# itrope-serial-v05.net
KiCad netlist of a schematic drawn in EAGLE
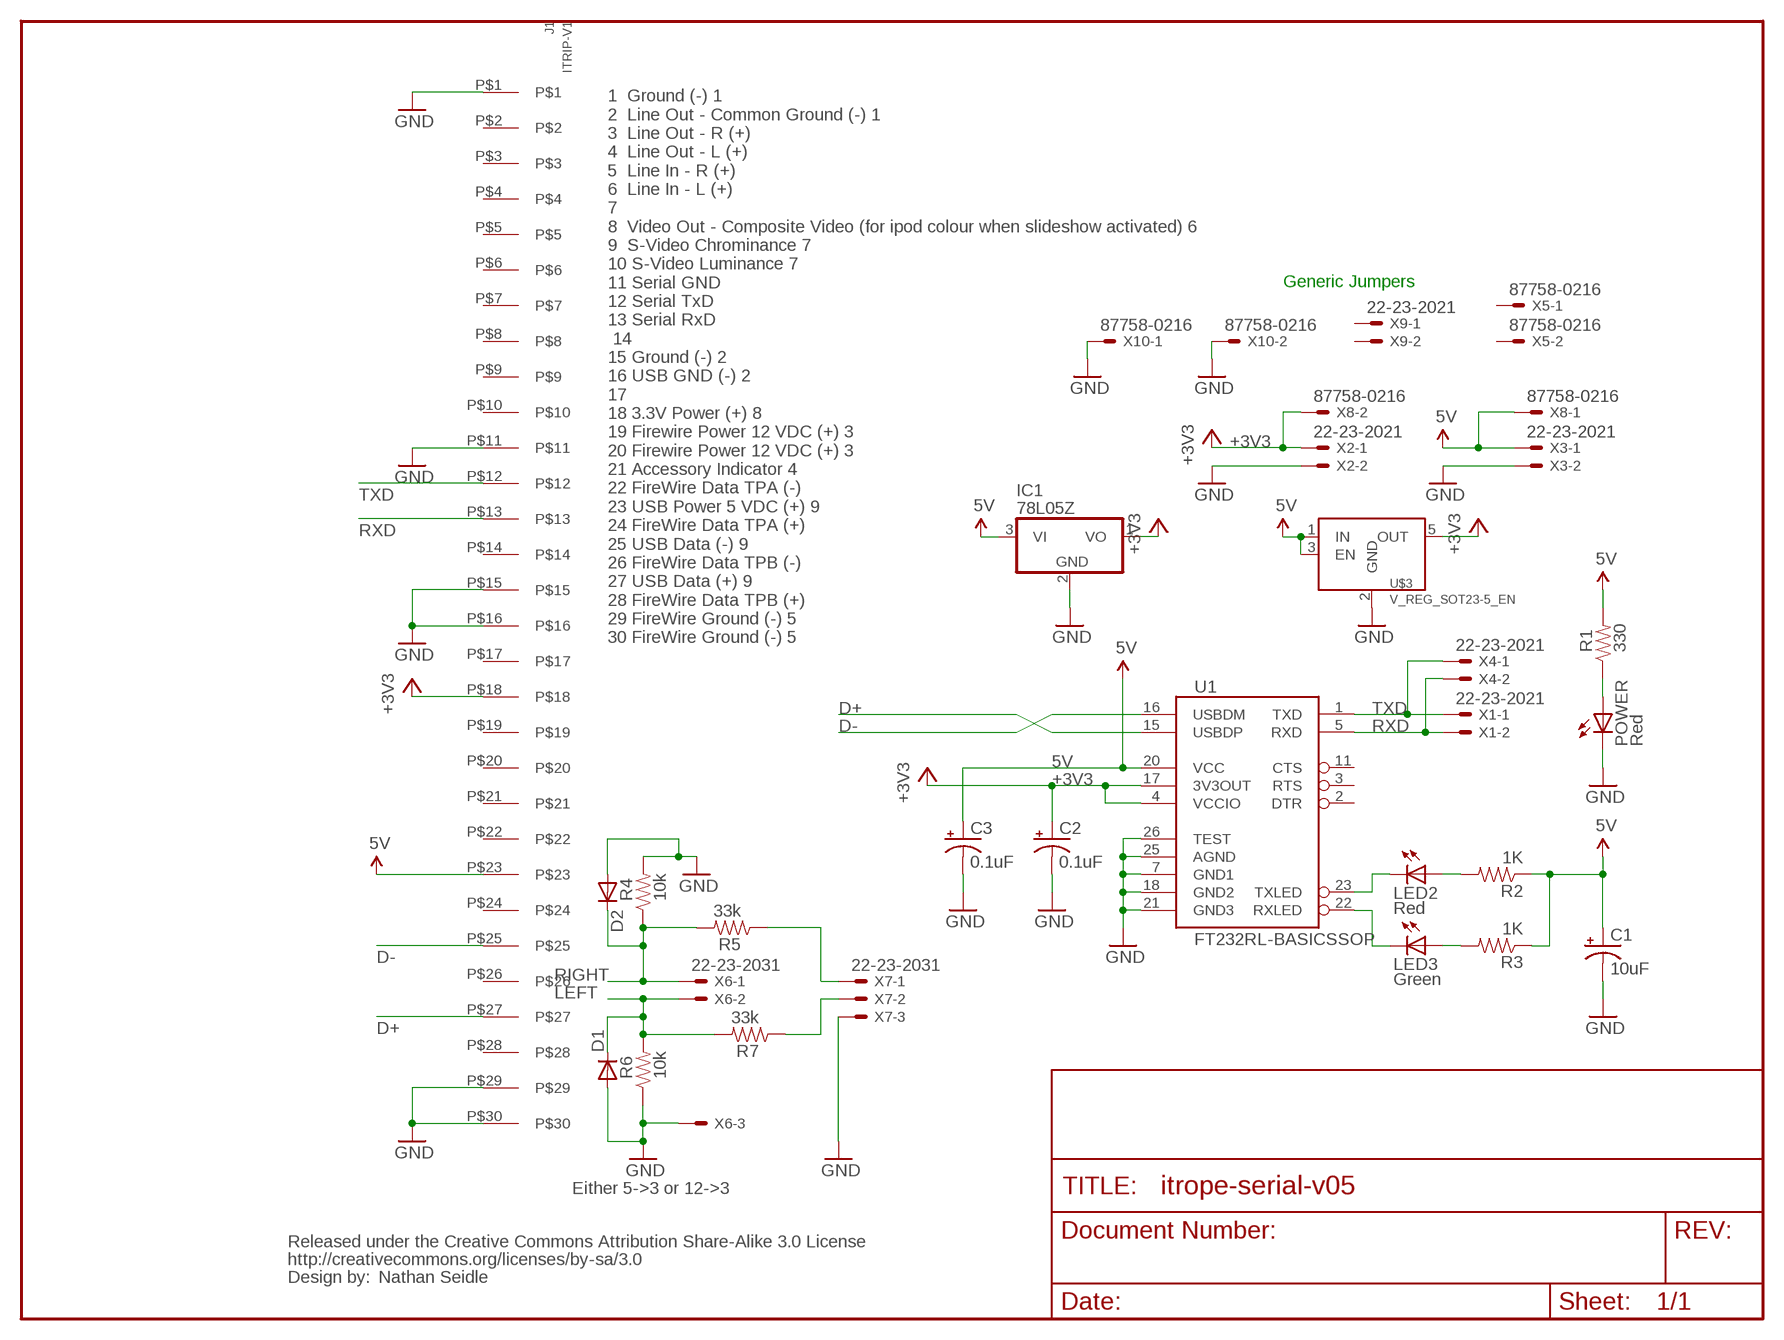
[diagram p0: schematic, sheet 1]

(export (version "E")
  (design (tool "Eeschema 10.0.6"))
  (components
    (comp (ref "C1")
      (value "10uF")
      (footprint "eagle-import:E2,5-5")
      (libsource (lib "eagle-import") (part "CPOL-USE2.5-5"))
    )
    (comp (ref "C2")
      (value "0.1uF")
      (footprint "eagle-import:E2,5-5")
      (libsource (lib "eagle-import") (part "CPOL-USE2.5-5"))
    )
    (comp (ref "C3")
      (value "0.1uF")
      (footprint "eagle-import:E2,5-5")
      (libsource (lib "eagle-import") (part "CPOL-USE2.5-5"))
    )
    (comp (ref "D1")
      (value "DIODESOD")
      (footprint "eagle-import:SOD-323")
      (libsource (lib "eagle-import") (part "DIODESOD"))
    )
    (comp (ref "D2")
      (value "DIODESOD")
      (footprint "eagle-import:SOD-323")
      (libsource (lib "eagle-import") (part "DIODESOD"))
    )
    (comp (ref "IC1")
      (value "78L05Z")
      (footprint "eagle-import:TO92")
      (libsource (lib "eagle-import") (part "78ZL05"))
    )
    (comp (ref "J1")
      (value "ITRIP-V1")
      (footprint "eagle-import:30PINEDGE+ITRIP")
      (libsource (lib "eagle-import") (part "ITRIP-V1"))
    )
    (comp (ref "LED2")
      (value "Red")
      (footprint "eagle-import:LED-0603")
      (libsource (lib "eagle-import") (part "LED0603"))
    )
    (comp (ref "LED3")
      (value "Green")
      (footprint "eagle-import:LED-0603")
      (libsource (lib "eagle-import") (part "LED0603"))
    )
    (comp (ref "POWER")
      (value "Red")
      (footprint "eagle-import:LED-0603")
      (libsource (lib "eagle-import") (part "LED0603"))
    )
    (comp (ref "R1")
      (value "330")
      (footprint "eagle-import:C0402")
      (libsource (lib "eagle-import") (part "RESISTOR0402"))
    )
    (comp (ref "R2")
      (value "1K")
      (footprint "eagle-import:C0402")
      (libsource (lib "eagle-import") (part "RESISTOR0402"))
    )
    (comp (ref "R3")
      (value "1K")
      (footprint "eagle-import:C0402")
      (libsource (lib "eagle-import") (part "RESISTOR0402"))
    )
    (comp (ref "R4")
      (value "10k")
      (footprint "eagle-import:C0402")
      (libsource (lib "eagle-import") (part "RESISTOR0402"))
    )
    (comp (ref "R5")
      (value "33k")
      (footprint "eagle-import:C0402")
      (libsource (lib "eagle-import") (part "RESISTOR0402"))
    )
    (comp (ref "R6")
      (value "10k")
      (footprint "eagle-import:C0402")
      (libsource (lib "eagle-import") (part "RESISTOR0402"))
    )
    (comp (ref "R7")
      (value "33k")
      (footprint "eagle-import:C0402")
      (libsource (lib "eagle-import") (part "RESISTOR0402"))
    )
    (comp (ref "U$3")
      (value "V_REG_SOT23-5_EN")
      (footprint "eagle-import:SOT23-5")
      (libsource (lib "eagle-import") (part "V_REG_SOT23-5_EN"))
    )
    (comp (ref "U$9")
      (value "CREATIVE_COMMONS")
      (footprint "eagle-import:CREATIVE_COMMONS")
      (libsource (lib "eagle-import") (part "CREATIVE_COMMONS"))
    )
    (comp (ref "U1")
      (value "FT232RL-BASICSSOP")
      (footprint "eagle-import:SSOP28DB")
      (libsource (lib "eagle-import") (part "FT232RL-BASICSSOP"))
    )
    (comp (ref "X1")
      (value "22-23-2021")
      (footprint "eagle-import:22-23-2021")
      (fields (field (name "MF") "MOLEX"))
      (libsource (lib "eagle-import") (part "22-23-2021"))
    )
    (comp (ref "X2")
      (value "22-23-2021")
      (footprint "eagle-import:22-23-2021")
      (fields (field (name "MF") "MOLEX"))
      (libsource (lib "eagle-import") (part "22-23-2021"))
    )
    (comp (ref "X3")
      (value "22-23-2021")
      (footprint "eagle-import:22-23-2021")
      (fields (field (name "MF") "MOLEX"))
      (libsource (lib "eagle-import") (part "22-23-2021"))
    )
    (comp (ref "X4")
      (value "22-23-2021")
      (footprint "eagle-import:22-23-2021")
      (fields (field (name "MF") "MOLEX"))
      (libsource (lib "eagle-import") (part "22-23-2021"))
    )
    (comp (ref "X5")
      (value "87758-0216")
      (footprint "eagle-import:87758-0216")
      (libsource (lib "eagle-import") (part "87758-0216"))
    )
    (comp (ref "X6")
      (value "22-23-2031")
      (footprint "eagle-import:22-23-2031")
      (fields (field (name "MF") "MOLEX"))
      (libsource (lib "eagle-import") (part "22-23-2031"))
    )
    (comp (ref "X7")
      (value "22-23-2031")
      (footprint "eagle-import:22-23-2031")
      (fields (field (name "MF") "MOLEX"))
      (libsource (lib "eagle-import") (part "22-23-2031"))
    )
    (comp (ref "X8")
      (value "87758-0216")
      (footprint "eagle-import:87758-0216")
      (libsource (lib "eagle-import") (part "87758-0216"))
    )
    (comp (ref "X9")
      (value "22-23-2021")
      (footprint "eagle-import:22-23-2021")
      (fields (field (name "MF") "MOLEX"))
      (libsource (lib "eagle-import") (part "22-23-2021"))
    )
    (comp (ref "X10")
      (value "87758-0216")
      (footprint "eagle-import:87758-0216")
      (libsource (lib "eagle-import") (part "87758-0216"))
    )
  )
  (nets
    (net (code "1") (name "+3V3") (class "Default")
      (node (ref "C2") (pin "+") (pinfunction "+_+") (pintype "passive"))
      (node (ref "IC1") (pin "1") (pinfunction "VO_1") (pintype "passive"))
      (node (ref "J1") (pin "P$18") (pinfunction "P$18_P$18") (pintype "bidirectional"))
      (node (ref "U$3") (pin "5") (pinfunction "OUT_5") (pintype "passive"))
      (node (ref "U1") (pin "17") (pinfunction "3V3OUT_17") (pintype "output"))
      (node (ref "U1") (pin "4") (pinfunction "VCCIO_4") (pintype "power_in"))
      (node (ref "X2") (pin "1") (pinfunction "S_1") (pintype "passive"))
      (node (ref "X8") (pin "2") (pinfunction "S_2") (pintype "passive"))
    )
    (net (code "2") (name "/D+") (class "Default")
      (node (ref "J1") (pin "P$27") (pinfunction "P$27_P$27") (pintype "bidirectional"))
      (node (ref "U1") (pin "15") (pinfunction "USBDP_15") (pintype "bidirectional"))
    )
    (net (code "3") (name "/D-") (class "Default")
      (node (ref "J1") (pin "P$25") (pinfunction "P$25_P$25") (pintype "bidirectional"))
      (node (ref "U1") (pin "16") (pinfunction "USBDM_16") (pintype "bidirectional"))
    )
    (net (code "4") (name "/LEFT") (class "Default")
      (node (ref "D1") (pin "1") (pinfunction "C_1") (pintype "passive"))
      (node (ref "R6") (pin "2") (pinfunction "2_2") (pintype "passive"))
      (node (ref "R7") (pin "2") (pinfunction "2_2") (pintype "passive"))
      (node (ref "X6") (pin "2") (pinfunction "S_2") (pintype "passive"))
    )
    (net (code "5") (name "/RIGHT") (class "Default")
      (node (ref "D2") (pin "1") (pinfunction "C_1") (pintype "passive"))
      (node (ref "R4") (pin "1") (pinfunction "1_1") (pintype "passive"))
      (node (ref "R5") (pin "2") (pinfunction "2_2") (pintype "passive"))
      (node (ref "X6") (pin "1") (pinfunction "S_1") (pintype "passive"))
    )
    (net (code "6") (name "/RXD") (class "Default")
      (node (ref "J1") (pin "P$13") (pinfunction "P$13_P$13") (pintype "bidirectional"))
      (node (ref "U1") (pin "5") (pinfunction "RXD_5") (pintype "input"))
      (node (ref "X1") (pin "2") (pinfunction "S_2") (pintype "passive"))
      (node (ref "X4") (pin "2") (pinfunction "S_2") (pintype "passive"))
    )
    (net (code "7") (name "/TXD") (class "Default")
      (node (ref "J1") (pin "P$12") (pinfunction "P$12_P$12") (pintype "bidirectional"))
      (node (ref "U1") (pin "1") (pinfunction "TXD_1") (pintype "output"))
      (node (ref "X1") (pin "1") (pinfunction "S_1") (pintype "passive"))
      (node (ref "X4") (pin "1") (pinfunction "S_1") (pintype "passive"))
    )
    (net (code "8") (name "5V") (class "Default")
      (node (ref "C1") (pin "+") (pinfunction "+_+") (pintype "passive"))
      (node (ref "C3") (pin "+") (pinfunction "+_+") (pintype "passive"))
      (node (ref "IC1") (pin "3") (pinfunction "VI_3") (pintype "input"))
      (node (ref "J1") (pin "P$23") (pinfunction "P$23_P$23") (pintype "bidirectional"))
      (node (ref "R1") (pin "2") (pinfunction "2_2") (pintype "passive"))
      (node (ref "R2") (pin "1") (pinfunction "1_1") (pintype "passive"))
      (node (ref "R3") (pin "1") (pinfunction "1_1") (pintype "passive"))
      (node (ref "U$3") (pin "1") (pinfunction "IN_1") (pintype "input"))
      (node (ref "U$3") (pin "3") (pinfunction "EN_3") (pintype "input"))
      (node (ref "U1") (pin "20") (pinfunction "VCC_20") (pintype "power_in"))
      (node (ref "X3") (pin "1") (pinfunction "S_1") (pintype "passive"))
      (node (ref "X8") (pin "1") (pinfunction "S_1") (pintype "passive"))
    )
    (net (code "9") (name "GND") (class "Default")
      (node (ref "C1") (pin "-") (pinfunction "-_-") (pintype "passive"))
      (node (ref "C2") (pin "-") (pinfunction "-_-") (pintype "passive"))
      (node (ref "C3") (pin "-") (pinfunction "-_-") (pintype "passive"))
      (node (ref "D1") (pin "2") (pinfunction "A_2") (pintype "passive"))
      (node (ref "D2") (pin "2") (pinfunction "A_2") (pintype "passive"))
      (node (ref "IC1") (pin "2") (pinfunction "GND_2") (pintype "passive"))
      (node (ref "J1") (pin "P$1") (pinfunction "P$1_P$1") (pintype "bidirectional"))
      (node (ref "J1") (pin "P$11") (pinfunction "P$11_P$11") (pintype "bidirectional"))
      (node (ref "J1") (pin "P$15") (pinfunction "P$15_P$15") (pintype "bidirectional"))
      (node (ref "J1") (pin "P$16") (pinfunction "P$16_P$16") (pintype "bidirectional"))
      (node (ref "J1") (pin "P$29") (pinfunction "P$29_P$29") (pintype "bidirectional"))
      (node (ref "J1") (pin "P$30") (pinfunction "P$30_P$30") (pintype "bidirectional"))
      (node (ref "POWER") (pin "C") (pinfunction "C_C") (pintype "passive"))
      (node (ref "R4") (pin "2") (pinfunction "2_2") (pintype "passive"))
      (node (ref "R6") (pin "1") (pinfunction "1_1") (pintype "passive"))
      (node (ref "U$3") (pin "2") (pinfunction "GND_2") (pintype "input"))
      (node (ref "U1") (pin "18") (pinfunction "GND2_18") (pintype "power_in"))
      (node (ref "U1") (pin "21") (pinfunction "GND3_21") (pintype "power_in"))
      (node (ref "U1") (pin "25") (pinfunction "AGND_25") (pintype "power_in"))
      (node (ref "U1") (pin "26") (pinfunction "TEST_26") (pintype "input"))
      (node (ref "U1") (pin "7") (pinfunction "GND1_7") (pintype "power_in"))
      (node (ref "X10") (pin "1") (pinfunction "S_1") (pintype "passive"))
      (node (ref "X10") (pin "2") (pinfunction "S_2") (pintype "passive"))
      (node (ref "X2") (pin "2") (pinfunction "S_2") (pintype "passive"))
      (node (ref "X3") (pin "2") (pinfunction "S_2") (pintype "passive"))
      (node (ref "X6") (pin "3") (pinfunction "S_3") (pintype "passive"))
      (node (ref "X7") (pin "3") (pinfunction "S_3") (pintype "passive"))
    )
    (net (code "10") (name "Net-(LED2-PadA)") (class "Default")
      (node (ref "LED2") (pin "A") (pinfunction "A_A") (pintype "passive"))
      (node (ref "R2") (pin "2") (pinfunction "2_2") (pintype "passive"))
    )
    (net (code "11") (name "Net-(LED3-PadA)") (class "Default")
      (node (ref "LED3") (pin "A") (pinfunction "A_A") (pintype "passive"))
      (node (ref "R3") (pin "2") (pinfunction "2_2") (pintype "passive"))
    )
    (net (code "12") (name "Net-(POWER-PadA)") (class "Default")
      (node (ref "POWER") (pin "A") (pinfunction "A_A") (pintype "passive"))
      (node (ref "R1") (pin "1") (pinfunction "1_1") (pintype "passive"))
    )
    (net (code "13") (name "Net-(U1-RXLED)") (class "Default")
      (node (ref "LED3") (pin "C") (pinfunction "C_C") (pintype "passive"))
      (node (ref "U1") (pin "22") (pinfunction "RXLED_22") (pintype "bidirectional"))
    )
    (net (code "14") (name "Net-(U1-TXLED)") (class "Default")
      (node (ref "LED2") (pin "C") (pinfunction "C_C") (pintype "passive"))
      (node (ref "U1") (pin "23") (pinfunction "TXLED_23") (pintype "bidirectional"))
    )
    (net (code "15") (name "Net-(X7A-S)") (class "Default")
      (node (ref "R5") (pin "1") (pinfunction "1_1") (pintype "passive"))
      (node (ref "X7") (pin "1") (pinfunction "S_1") (pintype "passive"))
    )
    (net (code "16") (name "Net-(X7B-S)") (class "Default")
      (node (ref "R7") (pin "1") (pinfunction "1_1") (pintype "passive"))
      (node (ref "X7") (pin "2") (pinfunction "S_2") (pintype "passive"))
    )
    (net (code "17") (name "unconnected-(J1-PadP$2)") (class "Default")
      (node (ref "J1") (pin "P$2") (pinfunction "P$2_P$2") (pintype "bidirectional"))
    )
    (net (code "18") (name "unconnected-(J1-PadP$3)") (class "Default")
      (node (ref "J1") (pin "P$3") (pinfunction "P$3_P$3") (pintype "bidirectional"))
    )
    (net (code "19") (name "unconnected-(J1-PadP$4)") (class "Default")
      (node (ref "J1") (pin "P$4") (pinfunction "P$4_P$4") (pintype "bidirectional"))
    )
    (net (code "20") (name "unconnected-(J1-PadP$5)") (class "Default")
      (node (ref "J1") (pin "P$5") (pinfunction "P$5_P$5") (pintype "bidirectional"))
    )
    (net (code "21") (name "unconnected-(J1-PadP$6)") (class "Default")
      (node (ref "J1") (pin "P$6") (pinfunction "P$6_P$6") (pintype "bidirectional"))
    )
    (net (code "22") (name "unconnected-(J1-PadP$7)") (class "Default")
      (node (ref "J1") (pin "P$7") (pinfunction "P$7_P$7") (pintype "bidirectional"))
    )
    (net (code "23") (name "unconnected-(J1-PadP$8)") (class "Default")
      (node (ref "J1") (pin "P$8") (pinfunction "P$8_P$8") (pintype "bidirectional"))
    )
    (net (code "24") (name "unconnected-(J1-PadP$9)") (class "Default")
      (node (ref "J1") (pin "P$9") (pinfunction "P$9_P$9") (pintype "bidirectional"))
    )
    (net (code "25") (name "unconnected-(J1-PadP$10)") (class "Default")
      (node (ref "J1") (pin "P$10") (pinfunction "P$10_P$10") (pintype "bidirectional"))
    )
    (net (code "26") (name "unconnected-(J1-PadP$14)") (class "Default")
      (node (ref "J1") (pin "P$14") (pinfunction "P$14_P$14") (pintype "bidirectional"))
    )
    (net (code "27") (name "unconnected-(J1-PadP$17)") (class "Default")
      (node (ref "J1") (pin "P$17") (pinfunction "P$17_P$17") (pintype "bidirectional"))
    )
    (net (code "28") (name "unconnected-(J1-PadP$19)") (class "Default")
      (node (ref "J1") (pin "P$19") (pinfunction "P$19_P$19") (pintype "bidirectional"))
    )
    (net (code "29") (name "unconnected-(J1-PadP$20)") (class "Default")
      (node (ref "J1") (pin "P$20") (pinfunction "P$20_P$20") (pintype "bidirectional"))
    )
    (net (code "30") (name "unconnected-(J1-PadP$21)") (class "Default")
      (node (ref "J1") (pin "P$21") (pinfunction "P$21_P$21") (pintype "bidirectional"))
    )
    (net (code "31") (name "unconnected-(J1-PadP$22)") (class "Default")
      (node (ref "J1") (pin "P$22") (pinfunction "P$22_P$22") (pintype "bidirectional"))
    )
    (net (code "32") (name "unconnected-(J1-PadP$24)") (class "Default")
      (node (ref "J1") (pin "P$24") (pinfunction "P$24_P$24") (pintype "bidirectional"))
    )
    (net (code "33") (name "unconnected-(J1-PadP$26)") (class "Default")
      (node (ref "J1") (pin "P$26") (pinfunction "P$26_P$26") (pintype "bidirectional"))
    )
    (net (code "34") (name "unconnected-(J1-PadP$28)") (class "Default")
      (node (ref "J1") (pin "P$28") (pinfunction "P$28_P$28") (pintype "bidirectional"))
    )
    (net (code "35") (name "unconnected-(U1-CTS-Pad11)") (class "Default")
      (node (ref "U1") (pin "11") (pinfunction "CTS_11") (pintype "bidirectional"))
    )
    (net (code "36") (name "unconnected-(U1-DTR-Pad2)") (class "Default")
      (node (ref "U1") (pin "2") (pinfunction "DTR_2") (pintype "bidirectional"))
    )
    (net (code "37") (name "unconnected-(U1-RTS-Pad3)") (class "Default")
      (node (ref "U1") (pin "3") (pinfunction "RTS_3") (pintype "bidirectional"))
    )
    (net (code "38") (name "unconnected-(X5A-S-Pad1)") (class "Default")
      (node (ref "X5") (pin "1") (pinfunction "S_1") (pintype "passive"))
    )
    (net (code "39") (name "unconnected-(X5B-S-Pad2)") (class "Default")
      (node (ref "X5") (pin "2") (pinfunction "S_2") (pintype "passive"))
    )
    (net (code "40") (name "unconnected-(X9A-S-Pad1)") (class "Default")
      (node (ref "X9") (pin "1") (pinfunction "S_1") (pintype "passive"))
    )
    (net (code "41") (name "unconnected-(X9B-S-Pad2)") (class "Default")
      (node (ref "X9") (pin "2") (pinfunction "S_2") (pintype "passive"))
    )
  )
)
